# nufsr-motion-sensor.net
KiCad netlist of a schematic drawn in Altium Designer
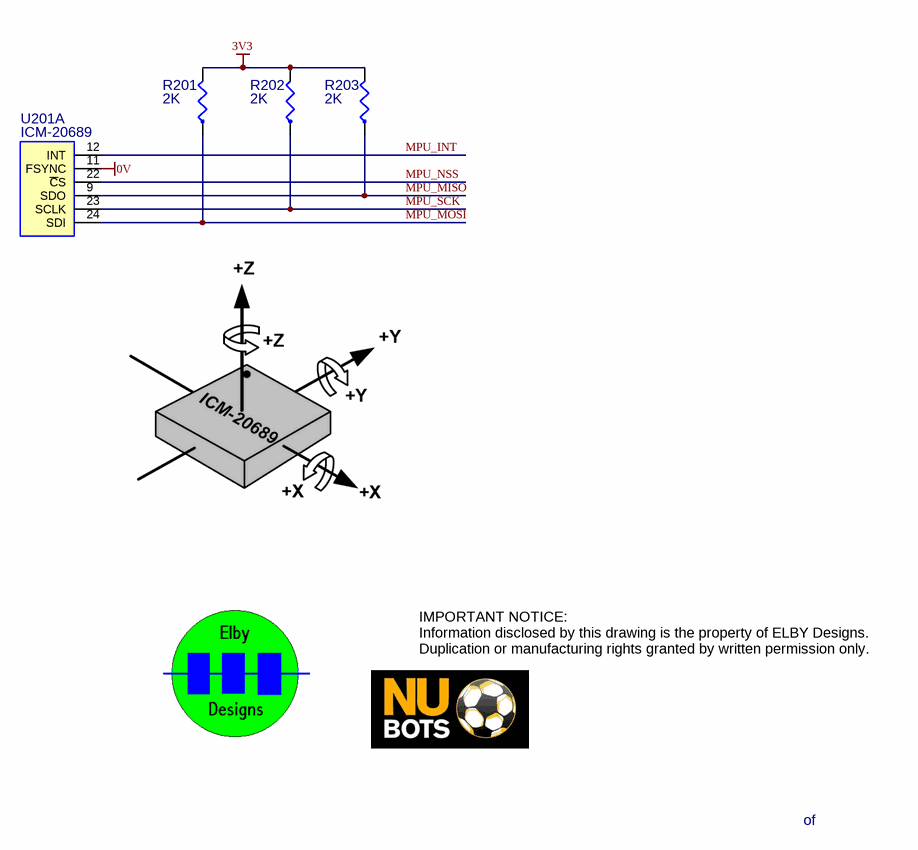
[diagram p0: nufsr-motion-sensor.schdoc]

(export (version "E")
  (design (tool "Eeschema 10.0.6"))
  (components
    (comp (ref "R201")
      (value "2K")
      (footprint "0603(LB)")
      (description "0.5W 1% Metal Film Resistor")
      (libsource (lib "resistor") (part "RM-2K(LB)"))
    )
    (comp (ref "R202")
      (value "2K")
      (footprint "0603(LB)")
      (description "0.5W 1% Metal Film Resistor")
      (libsource (lib "resistor") (part "RM-2K(LB)"))
    )
    (comp (ref "R203")
      (value "2K")
      (footprint "0603(LB)")
      (description "0.5W 1% Metal Film Resistor")
      (libsource (lib "resistor") (part "RM-2K(LB)"))
    )
    (comp (ref "U201")
      (value "ICM-20689")
      (footprint "QFN-24")
      (description "Motion Tracking")
      (libsource (lib "NuBots") (part "ICM-20869"))
    )
  )
  (nets
    (net (code "1") (name "/MPU_INT") (class "Default")
      (node (ref "U201") (pin "12") (pinfunction "INT_12") (pintype "passive"))
    )
    (net (code "2") (name "/MPU_MISO") (class "Default")
      (node (ref "R203") (pin "1") (pinfunction "1_1") (pintype "passive"))
      (node (ref "U201") (pin "9") (pinfunction "SDO_9") (pintype "passive"))
    )
    (net (code "3") (name "/MPU_MOSI") (class "Default")
      (node (ref "R201") (pin "1") (pinfunction "1_1") (pintype "passive"))
      (node (ref "U201") (pin "24") (pinfunction "SDI_24") (pintype "passive"))
    )
    (net (code "4") (name "/MPU_NSS") (class "Default")
      (node (ref "U201") (pin "22") (pinfunction "~{C}S_22") (pintype "passive"))
    )
    (net (code "5") (name "/MPU_SCK") (class "Default")
      (node (ref "R202") (pin "1") (pinfunction "1_1") (pintype "passive"))
      (node (ref "U201") (pin "23") (pinfunction "SCLK_23") (pintype "passive"))
    )
    (net (code "6") (name "0V") (class "Default")
      (node (ref "U201") (pin "11") (pinfunction "FSYNC_11") (pintype "passive"))
    )
    (net (code "7") (name "3V3") (class "Default")
      (node (ref "R201") (pin "2") (pinfunction "2_2") (pintype "passive"))
      (node (ref "R202") (pin "2") (pinfunction "2_2") (pintype "passive"))
      (node (ref "R203") (pin "2") (pinfunction "2_2") (pintype "passive"))
    )
  )
)
